# Serial_CAN_Bus.net
KiCad netlist of a schematic drawn in EAGLE
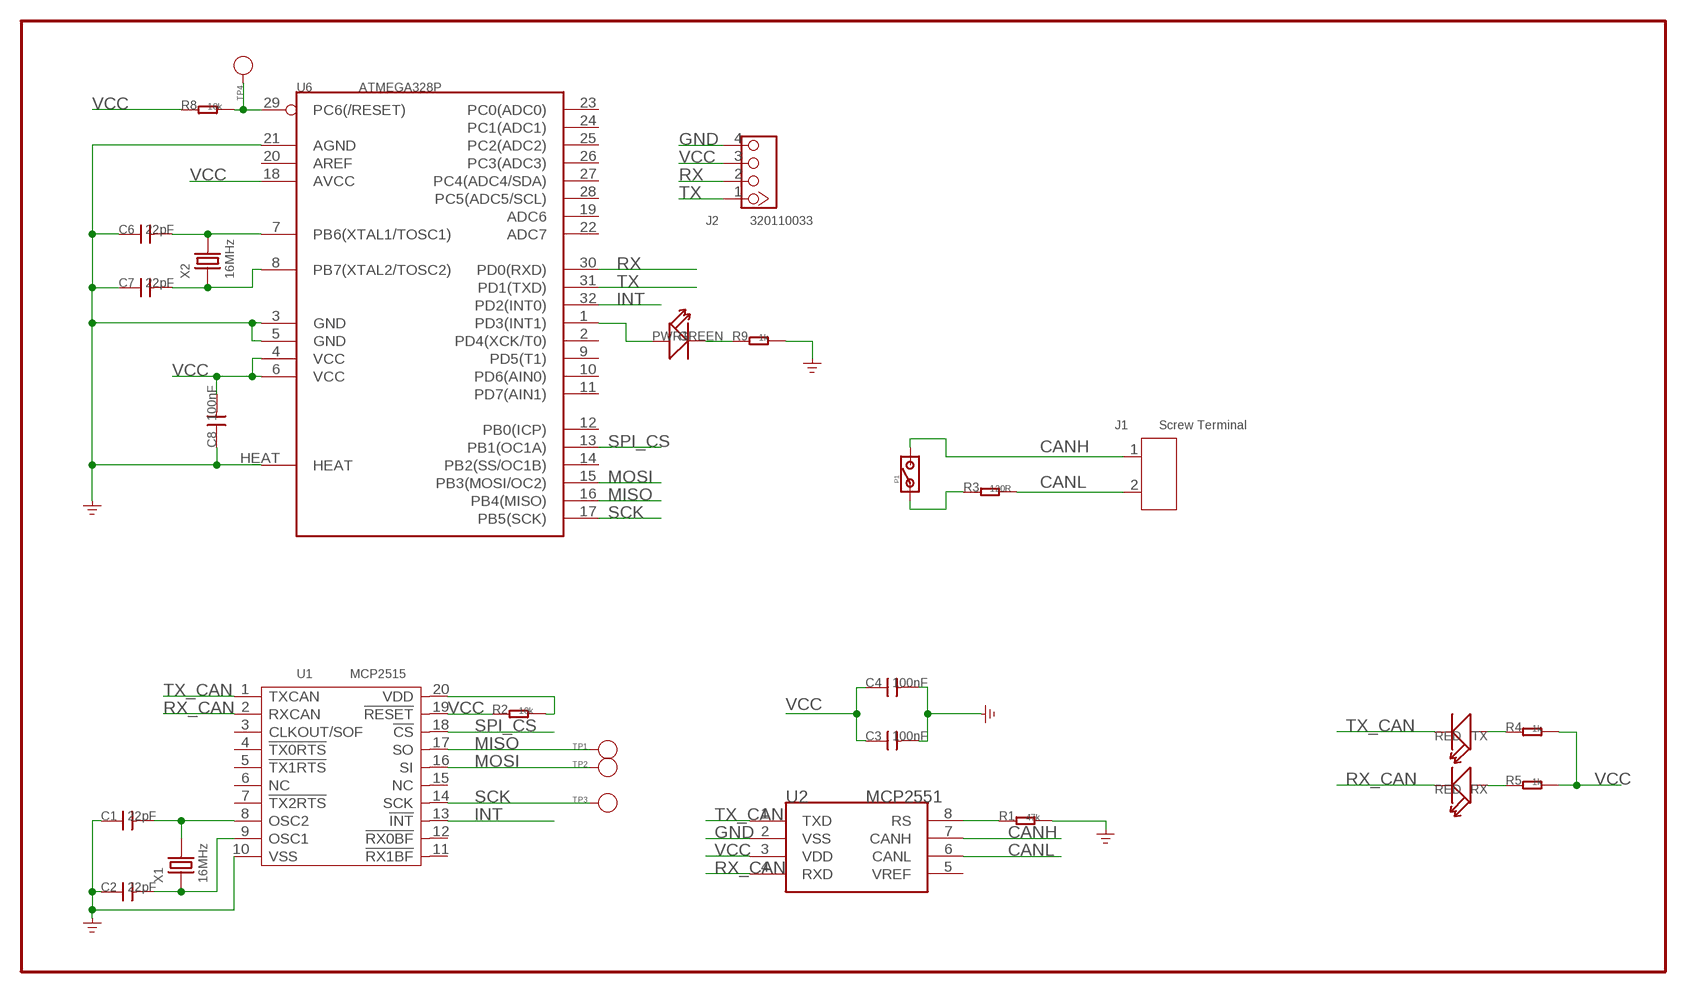
[diagram p0: schematic, sheet 1]

(export (version "E")
  (design (tool "Eeschema 10.0.6"))
  (components
    (comp (ref "C1")
      (value "22pF")
      (footprint "eagle-import:0603")
      (libsource (lib "eagle-import") (part "C-0603"))
    )
    (comp (ref "C2")
      (value "22pF")
      (footprint "eagle-import:0603")
      (libsource (lib "eagle-import") (part "C-0603"))
    )
    (comp (ref "C3")
      (value "100nF")
      (footprint "eagle-import:0603")
      (libsource (lib "eagle-import") (part "C-0603"))
    )
    (comp (ref "C4")
      (value "100nF")
      (footprint "eagle-import:0603")
      (libsource (lib "eagle-import") (part "C-0603"))
    )
    (comp (ref "C6")
      (value "22pF")
      (footprint "eagle-import:0603")
      (libsource (lib "eagle-import") (part "C-0603"))
    )
    (comp (ref "C7")
      (value "22pF")
      (footprint "eagle-import:0603")
      (libsource (lib "eagle-import") (part "C-0603"))
    )
    (comp (ref "C8")
      (value "100nF")
      (footprint "eagle-import:0603")
      (libsource (lib "eagle-import") (part "C-0603"))
    )
    (comp (ref "J1")
      (value "Screw Terminal")
      (footprint "eagle-import:2P-3.5")
      (libsource (lib "eagle-import") (part "SCREW-TERMINAL-2P'3.5'"))
    )
    (comp (ref "J2")
      (value "320110033")
      (footprint "eagle-import:HW4-2.0")
      (libsource (lib "eagle-import") (part "GROVE-CONNECTOR-DIP-2.0"))
    )
    (comp (ref "P1")
      (value "PAD-JUMPER-2P")
      (footprint "eagle-import:2P-SMD-1.78X1.27")
      (libsource (lib "eagle-import") (part "PAD-JUMPER-2P"))
    )
    (comp (ref "PWR1")
      (value "GREEN")
      (footprint "eagle-import:LED-0603")
      (libsource (lib "eagle-import") (part "LED'0603'"))
    )
    (comp (ref "R1")
      (value "47k")
      (footprint "eagle-import:0603")
      (libsource (lib "eagle-import") (part "R-0603"))
    )
    (comp (ref "R2")
      (value "10k")
      (footprint "eagle-import:0603")
      (libsource (lib "eagle-import") (part "R-0603"))
    )
    (comp (ref "R3")
      (value "120R")
      (footprint "eagle-import:0603")
      (libsource (lib "eagle-import") (part "R-0603"))
    )
    (comp (ref "R4")
      (value "1k")
      (footprint "eagle-import:0603")
      (libsource (lib "eagle-import") (part "R-0603"))
    )
    (comp (ref "R5")
      (value "1k")
      (footprint "eagle-import:0603")
      (libsource (lib "eagle-import") (part "R-0603"))
    )
    (comp (ref "R8")
      (value "10k")
      (footprint "eagle-import:0603")
      (libsource (lib "eagle-import") (part "R-0603"))
    )
    (comp (ref "R9")
      (value "1k")
      (footprint "eagle-import:0603")
      (libsource (lib "eagle-import") (part "R-0603"))
    )
    (comp (ref "RX")
      (value "RED")
      (footprint "eagle-import:LED-0603")
      (libsource (lib "eagle-import") (part "LED'0603'"))
    )
    (comp (ref "TP1")
      (value "PAD-TEST-POINT'4545'")
      (footprint "eagle-import:TP_4545")
      (fields (field (name "PARTNO") "DNP"))
      (libsource (lib "eagle-import") (part "PAD-TEST-POINT'4545'"))
    )
    (comp (ref "TP2")
      (value "PAD-TEST-POINT'4545'")
      (footprint "eagle-import:TP_4545")
      (fields (field (name "PARTNO") "DNP"))
      (libsource (lib "eagle-import") (part "PAD-TEST-POINT'4545'"))
    )
    (comp (ref "TP3")
      (value "PAD-TEST-POINT'4545'")
      (footprint "eagle-import:TP_4545")
      (fields (field (name "PARTNO") "DNP"))
      (libsource (lib "eagle-import") (part "PAD-TEST-POINT'4545'"))
    )
    (comp (ref "TP4")
      (value "PAD-TEST-POINT'4545'")
      (footprint "eagle-import:TP_4545")
      (fields (field (name "PARTNO") "DNP"))
      (libsource (lib "eagle-import") (part "PAD-TEST-POINT'4545'"))
    )
    (comp (ref "TX")
      (value "RED")
      (footprint "eagle-import:LED-0603")
      (libsource (lib "eagle-import") (part "LED'0603'"))
    )
    (comp (ref "U1")
      (value "MCP2515")
      (footprint "eagle-import:TSSOP20-0.65-6.5X4.4MM")
      (libsource (lib "eagle-import") (part "MCP2515'ST'"))
    )
    (comp (ref "U2")
      (value "MCP2551")
      (footprint "eagle-import:SOIC8-6.0")
      (libsource (lib "eagle-import") (part "MCP2551-SOIC8"))
    )
    (comp (ref "U6")
      (value "ATMEGA328P")
      (footprint "eagle-import:MLF32X")
      (libsource (lib "eagle-import") (part "MEGA8"))
    )
    (comp (ref "X1")
      (value "16MHz")
      (footprint "eagle-import:X2-SMD-5.0X3.2X1.3MM")
      (libsource (lib "eagle-import") (part "CRYSTAL-2P'5032'"))
    )
    (comp (ref "X2")
      (value "16MHz")
      (footprint "eagle-import:X2-SMD-5.0X3.2X1.3MM")
      (libsource (lib "eagle-import") (part "CRYSTAL-2P'5032'"))
    )
  )
  (nets
    (net (code "1") (name "CANH") (class "Default")
      (node (ref "J1") (pin "1") (pinfunction "1_1") (pintype "bidirectional"))
      (node (ref "P1") (pin "2") (pinfunction "2_2") (pintype "bidirectional"))
      (node (ref "U2") (pin "7") (pinfunction "CANH_7") (pintype "bidirectional"))
    )
    (net (code "2") (name "CANL") (class "Default")
      (node (ref "J1") (pin "2") (pinfunction "2_2") (pintype "bidirectional"))
      (node (ref "R3") (pin "2") (pinfunction "2_2") (pintype "passive"))
      (node (ref "U2") (pin "6") (pinfunction "CANL_6") (pintype "bidirectional"))
    )
    (net (code "3") (name "GND") (class "Default")
      (node (ref "C1") (pin "1") (pinfunction "1_1") (pintype "passive"))
      (node (ref "C2") (pin "1") (pinfunction "1_1") (pintype "passive"))
      (node (ref "C3") (pin "2") (pinfunction "2_2") (pintype "passive"))
      (node (ref "C4") (pin "2") (pinfunction "2_2") (pintype "passive"))
      (node (ref "C6") (pin "1") (pinfunction "1_1") (pintype "passive"))
      (node (ref "C7") (pin "1") (pinfunction "1_1") (pintype "passive"))
      (node (ref "C8") (pin "1") (pinfunction "1_1") (pintype "passive"))
      (node (ref "J2") (pin "4") (pinfunction "4_4") (pintype "bidirectional"))
      (node (ref "R1") (pin "2") (pinfunction "2_2") (pintype "passive"))
      (node (ref "R9") (pin "2") (pinfunction "2_2") (pintype "passive"))
      (node (ref "U1") (pin "10") (pinfunction "VSS_10") (pintype "bidirectional"))
      (node (ref "U2") (pin "2") (pinfunction "VSS_2") (pintype "bidirectional"))
      (node (ref "U6") (pin "21") (pinfunction "AGND_21") (pintype "bidirectional"))
      (node (ref "U6") (pin "3") (pinfunction "GND_3") (pintype "bidirectional"))
      (node (ref "U6") (pin "5") (pinfunction "GND_5") (pintype "bidirectional"))
      (node (ref "U6") (pin "HEAT") (pinfunction "HEAT_HEAT") (pintype "bidirectional"))
    )
    (net (code "4") (name "INT") (class "Default")
      (node (ref "U1") (pin "13") (pinfunction "~{INT}_13") (pintype "bidirectional"))
      (node (ref "U6") (pin "32") (pinfunction "PD2(INT0)_32") (pintype "bidirectional"))
    )
    (net (code "5") (name "MISO") (class "Default")
      (node (ref "TP1") (pin "T") (pinfunction "T_T") (pintype "bidirectional"))
      (node (ref "U1") (pin "17") (pinfunction "SO_17") (pintype "bidirectional"))
      (node (ref "U6") (pin "16") (pinfunction "PB4(MISO)_16") (pintype "bidirectional"))
    )
    (net (code "6") (name "MOSI") (class "Default")
      (node (ref "TP2") (pin "T") (pinfunction "T_T") (pintype "bidirectional"))
      (node (ref "U1") (pin "16") (pinfunction "SI_16") (pintype "bidirectional"))
      (node (ref "U6") (pin "15") (pinfunction "PB3(MOSI/OC2)_15") (pintype "bidirectional"))
    )
    (net (code "7") (name "Net-(P1-Pad1)") (class "Default")
      (node (ref "P1") (pin "1") (pinfunction "1_1") (pintype "bidirectional"))
      (node (ref "R3") (pin "1") (pinfunction "1_1") (pintype "passive"))
    )
    (net (code "8") (name "Net-(PWR1-Pad-)") (class "Default")
      (node (ref "PWR1") (pin "-") (pinfunction "-_-") (pintype "passive"))
      (node (ref "R9") (pin "1") (pinfunction "1_1") (pintype "passive"))
    )
    (net (code "9") (name "Net-(R4-Pad1)") (class "Default")
      (node (ref "R4") (pin "1") (pinfunction "1_1") (pintype "passive"))
      (node (ref "TX") (pin "+") (pinfunction "+_+") (pintype "passive"))
    )
    (net (code "10") (name "Net-(R5-Pad1)") (class "Default")
      (node (ref "R5") (pin "1") (pinfunction "1_1") (pintype "passive"))
      (node (ref "RX") (pin "+") (pinfunction "+_+") (pintype "passive"))
    )
    (net (code "11") (name "Net-(U1-OSC1)") (class "Default")
      (node (ref "C2") (pin "2") (pinfunction "2_2") (pintype "passive"))
      (node (ref "U1") (pin "9") (pinfunction "OSC1_9") (pintype "bidirectional"))
      (node (ref "X1") (pin "1") (pinfunction "1_1") (pintype "passive"))
    )
    (net (code "12") (name "Net-(U1-OSC2)") (class "Default")
      (node (ref "C1") (pin "2") (pinfunction "2_2") (pintype "passive"))
      (node (ref "U1") (pin "8") (pinfunction "OSC2_8") (pintype "bidirectional"))
      (node (ref "X1") (pin "2") (pinfunction "2_2") (pintype "passive"))
    )
    (net (code "13") (name "Net-(U1-~{RESET})") (class "Default")
      (node (ref "R2") (pin "1") (pinfunction "1_1") (pintype "passive"))
      (node (ref "U1") (pin "19") (pinfunction "~{RESET}_19") (pintype "bidirectional"))
    )
    (net (code "14") (name "Net-(U2-RS)") (class "Default")
      (node (ref "R1") (pin "1") (pinfunction "1_1") (pintype "passive"))
      (node (ref "U2") (pin "8") (pinfunction "RS_8") (pintype "bidirectional"))
    )
    (net (code "15") (name "Net-(U6-PB6(XTAL1{slash}TOSC1))") (class "Default")
      (node (ref "C6") (pin "2") (pinfunction "2_2") (pintype "passive"))
      (node (ref "U6") (pin "7") (pinfunction "PB6(XTAL1/TOSC1)_7") (pintype "bidirectional"))
      (node (ref "X2") (pin "2") (pinfunction "2_2") (pintype "passive"))
    )
    (net (code "16") (name "Net-(U6-PB7(XTAL2{slash}TOSC2))") (class "Default")
      (node (ref "C7") (pin "2") (pinfunction "2_2") (pintype "passive"))
      (node (ref "U6") (pin "8") (pinfunction "PB7(XTAL2/TOSC2)_8") (pintype "bidirectional"))
      (node (ref "X2") (pin "1") (pinfunction "1_1") (pintype "passive"))
    )
    (net (code "17") (name "Net-(U6-PC6({slash}RESET))") (class "Default")
      (node (ref "R8") (pin "2") (pinfunction "2_2") (pintype "passive"))
      (node (ref "TP4") (pin "T") (pinfunction "T_T") (pintype "bidirectional"))
      (node (ref "U6") (pin "29") (pinfunction "PC6(/RESET)_29") (pintype "bidirectional"))
    )
    (net (code "18") (name "Net-(U6-PD3(INT1))") (class "Default")
      (node (ref "PWR1") (pin "+") (pinfunction "+_+") (pintype "passive"))
      (node (ref "U6") (pin "1") (pinfunction "PD3(INT1)_1") (pintype "bidirectional"))
    )
    (net (code "19") (name "RX") (class "Default")
      (node (ref "J2") (pin "2") (pinfunction "2_2") (pintype "bidirectional"))
      (node (ref "U6") (pin "30") (pinfunction "PD0(RXD)_30") (pintype "bidirectional"))
    )
    (net (code "20") (name "RX_CAN") (class "Default")
      (node (ref "RX") (pin "-") (pinfunction "-_-") (pintype "passive"))
      (node (ref "U1") (pin "2") (pinfunction "RXCAN_2") (pintype "bidirectional"))
      (node (ref "U2") (pin "4") (pinfunction "RXD_4") (pintype "bidirectional"))
    )
    (net (code "21") (name "SCK") (class "Default")
      (node (ref "TP3") (pin "T") (pinfunction "T_T") (pintype "bidirectional"))
      (node (ref "U1") (pin "14") (pinfunction "SCK_14") (pintype "bidirectional"))
      (node (ref "U6") (pin "17") (pinfunction "PB5(SCK)_17") (pintype "bidirectional"))
    )
    (net (code "22") (name "SPI_CS") (class "Default")
      (node (ref "U1") (pin "18") (pinfunction "~{CS}_18") (pintype "bidirectional"))
      (node (ref "U6") (pin "13") (pinfunction "PB1(OC1A)_13") (pintype "bidirectional"))
    )
    (net (code "23") (name "TX") (class "Default")
      (node (ref "J2") (pin "1") (pinfunction "1_1") (pintype "bidirectional"))
      (node (ref "U6") (pin "31") (pinfunction "PD1(TXD)_31") (pintype "bidirectional"))
    )
    (net (code "24") (name "TX_CAN") (class "Default")
      (node (ref "TX") (pin "-") (pinfunction "-_-") (pintype "passive"))
      (node (ref "U1") (pin "1") (pinfunction "TXCAN_1") (pintype "bidirectional"))
      (node (ref "U2") (pin "1") (pinfunction "TXD_1") (pintype "bidirectional"))
    )
    (net (code "25") (name "VCC") (class "Default")
      (node (ref "C3") (pin "1") (pinfunction "1_1") (pintype "passive"))
      (node (ref "C4") (pin "1") (pinfunction "1_1") (pintype "passive"))
      (node (ref "C8") (pin "2") (pinfunction "2_2") (pintype "passive"))
      (node (ref "J2") (pin "3") (pinfunction "3_3") (pintype "bidirectional"))
      (node (ref "R2") (pin "2") (pinfunction "2_2") (pintype "passive"))
      (node (ref "R4") (pin "2") (pinfunction "2_2") (pintype "passive"))
      (node (ref "R5") (pin "2") (pinfunction "2_2") (pintype "passive"))
      (node (ref "R8") (pin "1") (pinfunction "1_1") (pintype "passive"))
      (node (ref "U1") (pin "20") (pinfunction "VDD_20") (pintype "bidirectional"))
      (node (ref "U2") (pin "3") (pinfunction "VDD_3") (pintype "bidirectional"))
      (node (ref "U6") (pin "18") (pinfunction "AVCC_18") (pintype "bidirectional"))
      (node (ref "U6") (pin "4") (pinfunction "VCC_4") (pintype "bidirectional"))
      (node (ref "U6") (pin "6") (pinfunction "VCC_6") (pintype "bidirectional"))
    )
    (net (code "26") (name "unconnected-(U1-CLKOUT{slash}SOF-Pad3)") (class "Default")
      (node (ref "U1") (pin "3") (pinfunction "CLKOUT/SOF_3") (pintype "bidirectional"))
    )
    (net (code "27") (name "unconnected-(U1-NC-Pad6)") (class "Default")
      (node (ref "U1") (pin "6") (pinfunction "NC_6") (pintype "bidirectional"))
    )
    (net (code "28") (name "unconnected-(U1-NC-Pad15)") (class "Default")
      (node (ref "U1") (pin "15") (pinfunction "NC_15") (pintype "bidirectional"))
    )
    (net (code "29") (name "unconnected-(U1-~{RX0BF}-Pad12)") (class "Default")
      (node (ref "U1") (pin "12") (pinfunction "~{RX0BF}_12") (pintype "bidirectional"))
    )
    (net (code "30") (name "unconnected-(U1-~{RX1BF}-Pad11)") (class "Default")
      (node (ref "U1") (pin "11") (pinfunction "~{RX1BF}_11") (pintype "bidirectional"))
    )
    (net (code "31") (name "unconnected-(U1-~{TX0RTS}-Pad4)") (class "Default")
      (node (ref "U1") (pin "4") (pinfunction "~{TX0RTS}_4") (pintype "bidirectional"))
    )
    (net (code "32") (name "unconnected-(U1-~{TX1RTS}-Pad5)") (class "Default")
      (node (ref "U1") (pin "5") (pinfunction "~{TX1RTS}_5") (pintype "bidirectional"))
    )
    (net (code "33") (name "unconnected-(U1-~{TX2RTS}-Pad7)") (class "Default")
      (node (ref "U1") (pin "7") (pinfunction "~{TX2RTS}_7") (pintype "bidirectional"))
    )
    (net (code "34") (name "unconnected-(U2-VREF-Pad5)") (class "Default")
      (node (ref "U2") (pin "5") (pinfunction "VREF_5") (pintype "bidirectional"))
    )
    (net (code "35") (name "unconnected-(U6-ADC6-Pad19)") (class "Default")
      (node (ref "U6") (pin "19") (pinfunction "ADC6_19") (pintype "bidirectional"))
    )
    (net (code "36") (name "unconnected-(U6-ADC7-Pad22)") (class "Default")
      (node (ref "U6") (pin "22") (pinfunction "ADC7_22") (pintype "bidirectional"))
    )
    (net (code "37") (name "unconnected-(U6-AREF-Pad20)") (class "Default")
      (node (ref "U6") (pin "20") (pinfunction "AREF_20") (pintype "bidirectional"))
    )
    (net (code "38") (name "unconnected-(U6-PB0(ICP)-Pad12)") (class "Default")
      (node (ref "U6") (pin "12") (pinfunction "PB0(ICP)_12") (pintype "bidirectional"))
    )
    (net (code "39") (name "unconnected-(U6-PB2(SS{slash}OC1B)-Pad14)") (class "Default")
      (node (ref "U6") (pin "14") (pinfunction "PB2(SS/OC1B)_14") (pintype "bidirectional"))
    )
    (net (code "40") (name "unconnected-(U6-PC0(ADC0)-Pad23)") (class "Default")
      (node (ref "U6") (pin "23") (pinfunction "PC0(ADC0)_23") (pintype "bidirectional"))
    )
    (net (code "41") (name "unconnected-(U6-PC1(ADC1)-Pad24)") (class "Default")
      (node (ref "U6") (pin "24") (pinfunction "PC1(ADC1)_24") (pintype "bidirectional"))
    )
    (net (code "42") (name "unconnected-(U6-PC2(ADC2)-Pad25)") (class "Default")
      (node (ref "U6") (pin "25") (pinfunction "PC2(ADC2)_25") (pintype "bidirectional"))
    )
    (net (code "43") (name "unconnected-(U6-PC3(ADC3)-Pad26)") (class "Default")
      (node (ref "U6") (pin "26") (pinfunction "PC3(ADC3)_26") (pintype "bidirectional"))
    )
    (net (code "44") (name "unconnected-(U6-PC4(ADC4{slash}SDA)-Pad27)") (class "Default")
      (node (ref "U6") (pin "27") (pinfunction "PC4(ADC4/SDA)_27") (pintype "bidirectional"))
    )
    (net (code "45") (name "unconnected-(U6-PC5(ADC5{slash}SCL)-Pad28)") (class "Default")
      (node (ref "U6") (pin "28") (pinfunction "PC5(ADC5/SCL)_28") (pintype "bidirectional"))
    )
    (net (code "46") (name "unconnected-(U6-PD4(XCK{slash}T0)-Pad2)") (class "Default")
      (node (ref "U6") (pin "2") (pinfunction "PD4(XCK/T0)_2") (pintype "bidirectional"))
    )
    (net (code "47") (name "unconnected-(U6-PD5(T1)-Pad9)") (class "Default")
      (node (ref "U6") (pin "9") (pinfunction "PD5(T1)_9") (pintype "bidirectional"))
    )
    (net (code "48") (name "unconnected-(U6-PD6(AIN0)-Pad10)") (class "Default")
      (node (ref "U6") (pin "10") (pinfunction "PD6(AIN0)_10") (pintype "bidirectional"))
    )
    (net (code "49") (name "unconnected-(U6-PD7(AIN1)-Pad11)") (class "Default")
      (node (ref "U6") (pin "11") (pinfunction "PD7(AIN1)_11") (pintype "bidirectional"))
    )
  )
)
